# PCB1.net
KiCad netlist of a schematic drawn in Altium Designer
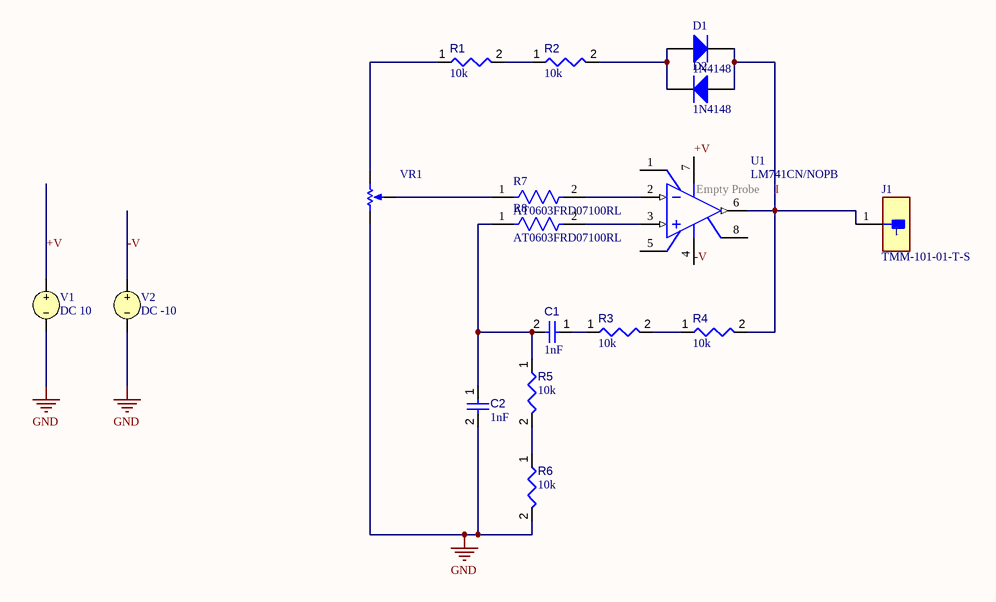
[diagram p0: PCB1.SchDoc]

(export (version "E")
  (design (tool "Eeschema 10.0.6"))
  (components
    (comp (ref "C1")
      (value "1nF")
      (footprint "CAPC0402(1005)33_L")
      (description "Chip Capacitor, 1nF +/-20%, 50V, 0402, Thickness 0.33 mm")
      (fields (field (name "TOLERANCE") "10%") (field (name "Comment") "Capacitor 1nF +/-20% 50V 0402"))
      (libsource (lib "Personal Use (GarablueX)") (part "CAP-NP-2"))
    )
    (comp (ref "C2")
      (value "1nF")
      (footprint "CAPC0402(1005)33_L")
      (description "Chip Capacitor, 1nF +/-20%, 50V, 0402, Thickness 0.33 mm")
      (fields (field (name "TOLERANCE") "10%") (field (name "Comment") "Capacitor 1nF +/-20% 50V 0402"))
      (libsource (lib "Personal Use (GarablueX)") (part "CAP-NP-2"))
    )
    (comp (ref "D1")
      (value "1N4148")
      (footprint "NXP-SOD27-2_V")
      (description "High Speed Diode, 100 V, 0.45 A, -65 to 175 degC, 2-Pin SOD27, RoHS, Bulk")
      (fields (field (name "POWER") "500mW") (field (name "MANUFACTURER") "Fairchild"))
      (libsource (lib "Personal Use (GarablueX)") (part "D-AK-2"))
    )
    (comp (ref "D2")
      (value "1N4148")
      (footprint "NXP-SOD27-2_V")
      (description "High Speed Diode, 100 V, 0.45 A, -65 to 175 degC, 2-Pin SOD27, RoHS, Bulk")
      (fields (field (name "POWER") "500mW") (field (name "MANUFACTURER") "Fairchild"))
      (libsource (lib "Personal Use (GarablueX)") (part "D-AK-2"))
    )
    (comp (ref "J1")
      (value "TMM-101-01-T-S")
      (footprint "FP-TMM-101-01-T-S-MFG")
      (description "CONN HEADER VERT 1POS")
      (libsource (lib "Altium Content Vault") (part "dd45045ce8184df9e99e12baf3f412c"))
    )
    (comp (ref "R1")
      (value "10k")
      (footprint "RESA60-630X240")
      (description "Axial Resistor, 10 KOhm, +/- 1%, 0.25 W, -55 to 155 degC, 2-Pin THD, RoHS, Bulk")
      (fields (field (name "TOLERANCE") "1%") (field (name "POWER") "250mW"))
      (libsource (lib "Personal Use (GarablueX)") (part "RES-2"))
    )
    (comp (ref "R2")
      (value "10k")
      (footprint "RESA60-630X240")
      (description "Axial Resistor, 10 KOhm, +/- 1%, 0.25 W, -55 to 155 degC, 2-Pin THD, RoHS, Bulk")
      (fields (field (name "TOLERANCE") "1%") (field (name "POWER") "250mW"))
      (libsource (lib "Personal Use (GarablueX)") (part "RES-2"))
    )
    (comp (ref "R3")
      (value "10k")
      (footprint "RESA60-630X240")
      (description "Axial Resistor, 10 KOhm, +/- 1%, 0.25 W, -55 to 155 degC, 2-Pin THD, RoHS, Bulk")
      (fields (field (name "TOLERANCE") "1%") (field (name "POWER") "250mW"))
      (libsource (lib "Personal Use (GarablueX)") (part "RES-2"))
    )
    (comp (ref "R4")
      (value "10k")
      (footprint "RESA60-630X240")
      (description "Axial Resistor, 10 KOhm, +/- 1%, 0.25 W, -55 to 155 degC, 2-Pin THD, RoHS, Bulk")
      (fields (field (name "TOLERANCE") "1%") (field (name "POWER") "250mW"))
      (libsource (lib "Personal Use (GarablueX)") (part "RES-2"))
    )
    (comp (ref "R5")
      (value "10k")
      (footprint "RESA60-630X240")
      (description "Axial Resistor, 10 KOhm, +/- 1%, 0.25 W, -55 to 155 degC, 2-Pin THD, RoHS, Bulk")
      (fields (field (name "TOLERANCE") "1%") (field (name "POWER") "250mW"))
      (libsource (lib "Personal Use (GarablueX)") (part "RES-2"))
    )
    (comp (ref "R6")
      (value "10k")
      (footprint "RESA60-630X240")
      (description "Axial Resistor, 10 KOhm, +/- 1%, 0.25 W, -55 to 155 degC, 2-Pin THD, RoHS, Bulk")
      (fields (field (name "TOLERANCE") "1%") (field (name "POWER") "250mW"))
      (libsource (lib "Personal Use (GarablueX)") (part "RES-2"))
    )
    (comp (ref "R7")
      (value "AT0603FRD07100RL")
      (footprint "FP-AT0603-MFG")
      (description "Thin Film Chip Resistors Automotive Grade 100Ω 1% 25ppm/°C 0603")
      (libsource (lib "Altium Content Vault") (part "1029c3af85768c4190bb7ad29bc67b5"))
    )
    (comp (ref "R8")
      (value "AT0603FRD07100RL")
      (footprint "FP-AT0603-MFG")
      (description "Thin Film Chip Resistors Automotive Grade 100Ω 1% 25ppm/°C 0603")
      (libsource (lib "Altium Content Vault") (part "1029c3af85768c4190bb7ad29bc67b5"))
    )
    (comp (ref "U1")
      (value "LM741CN/NOPB")
      (footprint "P0008A")
      (description "Operational Amplifier, 8-pin MDIP, Pb-Free")
      (fields (field (name "MANUFACTURER") "Texas Instruments"))
      (libsource (lib "Altium Content Vault") (part "AMP-OPA-LM741-8"))
    )
    (comp (ref "V1")
      (value "DC 10")
      (description "Voltage Source")
      (fields (field (name "PUBLISHER") "Altium Limited"))
      (libsource (lib "Simulation Generic Components") (part "VSRC"))
    )
    (comp (ref "V2")
      (value "DC -10")
      (description "Voltage Source")
      (fields (field (name "PUBLISHER") "Altium Limited"))
      (libsource (lib "Simulation Generic Components") (part "VSRC"))
    )
    (comp (ref "VR1")
      (value "3362P-1-103LF")
      (footprint "BOUR-3362P")
      (description "Square Trimpot(R) Trimming Potentiometer, 10 KOhm, 300 V, -55 to 125 degC, 3-Pin THD, RoHS, Tube")
      (fields (field (name "MANUFACTURER") "Bourns") (field (name "TOLERANCE") "10%"))
      (libsource (lib "Personal Use (GarablueX)") (part "RES-POT-3"))
    )
  )
  (nets
    (net (code "1") (name "/+V") (class "Default")
      (node (ref "U1") (pin "7") (pinfunction "V+_7") (pintype "power_in"))
      (node (ref "V1") (pin "1") (pinfunction "1_1") (pintype "passive"))
    )
    (net (code "2") (name "/-V") (class "Default")
      (node (ref "U1") (pin "4") (pinfunction "V-_4") (pintype "power_in"))
      (node (ref "V2") (pin "1") (pinfunction "1_1") (pintype "passive"))
    )
    (net (code "3") (name "GND") (class "Default")
      (node (ref "C2") (pin "2") (pinfunction "2_2") (pintype "passive"))
      (node (ref "R6") (pin "2") (pinfunction "2_2") (pintype "passive"))
      (node (ref "V1") (pin "2") (pinfunction "2_2") (pintype "passive"))
      (node (ref "V2") (pin "2") (pinfunction "2_2") (pintype "passive"))
      (node (ref "VR1") (pin "1") (pinfunction "CCW_1") (pintype "passive"))
    )
    (net (code "4") (name "Net-(C1-Pad1)") (class "Default")
      (node (ref "C1") (pin "1") (pinfunction "1_1") (pintype "passive"))
      (node (ref "R3") (pin "1") (pinfunction "1_1") (pintype "passive"))
    )
    (net (code "5") (name "Net-(C1-Pad2)") (class "Default")
      (node (ref "C1") (pin "2") (pinfunction "2_2") (pintype "passive"))
      (node (ref "C2") (pin "1") (pinfunction "1_1") (pintype "passive"))
      (node (ref "R5") (pin "1") (pinfunction "1_1") (pintype "passive"))
      (node (ref "R8") (pin "1") (pinfunction "1_1") (pintype "passive"))
    )
    (net (code "6") (name "Net-(D1-A)") (class "Default")
      (node (ref "D1") (pin "1") (pinfunction "A_1") (pintype "passive"))
      (node (ref "D2") (pin "2") (pinfunction "K_2") (pintype "passive"))
      (node (ref "R2") (pin "2") (pinfunction "2_2") (pintype "passive"))
    )
    (net (code "7") (name "Net-(D1-K)") (class "Default")
      (node (ref "D1") (pin "2") (pinfunction "K_2") (pintype "passive"))
      (node (ref "D2") (pin "1") (pinfunction "A_1") (pintype "passive"))
      (node (ref "J1") (pin "1") (pinfunction "1_1") (pintype "passive"))
      (node (ref "R4") (pin "2") (pinfunction "2_2") (pintype "passive"))
      (node (ref "U1") (pin "6") (pinfunction "OUT_6") (pintype "output"))
    )
    (net (code "8") (name "Net-(R1-Pad2)") (class "Default")
      (node (ref "R1") (pin "2") (pinfunction "2_2") (pintype "passive"))
      (node (ref "R2") (pin "1") (pinfunction "1_1") (pintype "passive"))
    )
    (net (code "9") (name "Net-(R3-Pad2)") (class "Default")
      (node (ref "R3") (pin "2") (pinfunction "2_2") (pintype "passive"))
      (node (ref "R4") (pin "1") (pinfunction "1_1") (pintype "passive"))
    )
    (net (code "10") (name "Net-(R5-Pad2)") (class "Default")
      (node (ref "R5") (pin "2") (pinfunction "2_2") (pintype "passive"))
      (node (ref "R6") (pin "1") (pinfunction "1_1") (pintype "passive"))
    )
    (net (code "11") (name "Net-(U1-IN+)") (class "Default")
      (node (ref "R8") (pin "2") (pinfunction "2_2") (pintype "passive"))
      (node (ref "U1") (pin "3") (pinfunction "IN+_3") (pintype "input"))
    )
    (net (code "12") (name "Net-(U1-IN-)") (class "Default")
      (node (ref "R7") (pin "2") (pinfunction "2_2") (pintype "passive"))
      (node (ref "U1") (pin "2") (pinfunction "IN-_2") (pintype "input"))
    )
    (net (code "13") (name "Net-(VR1-CW)") (class "Default")
      (node (ref "R1") (pin "1") (pinfunction "1_1") (pintype "passive"))
      (node (ref "VR1") (pin "3") (pinfunction "CW_3") (pintype "passive"))
    )
    (net (code "14") (name "Net-(VR1-S)") (class "Default")
      (node (ref "R7") (pin "1") (pinfunction "1_1") (pintype "passive"))
      (node (ref "VR1") (pin "2") (pinfunction "S_2") (pintype "passive"))
    )
    (net (code "15") (name "unconnected-(U1-NC-Pad8)") (class "Default")
      (node (ref "U1") (pin "8") (pinfunction "NC_8") (pintype "passive"))
    )
    (net (code "16") (name "unconnected-(U1-OFS_NULL-Pad1)") (class "Default")
      (node (ref "U1") (pin "1") (pinfunction "OFS_NULL_1") (pintype "passive"))
    )
    (net (code "17") (name "unconnected-(U1-OFS_NULL-Pad5)") (class "Default")
      (node (ref "U1") (pin "5") (pinfunction "OFS_NULL_5") (pintype "passive"))
    )
  )
)
